# DotIO.net
KiCad netlist of a schematic drawn in EAGLE
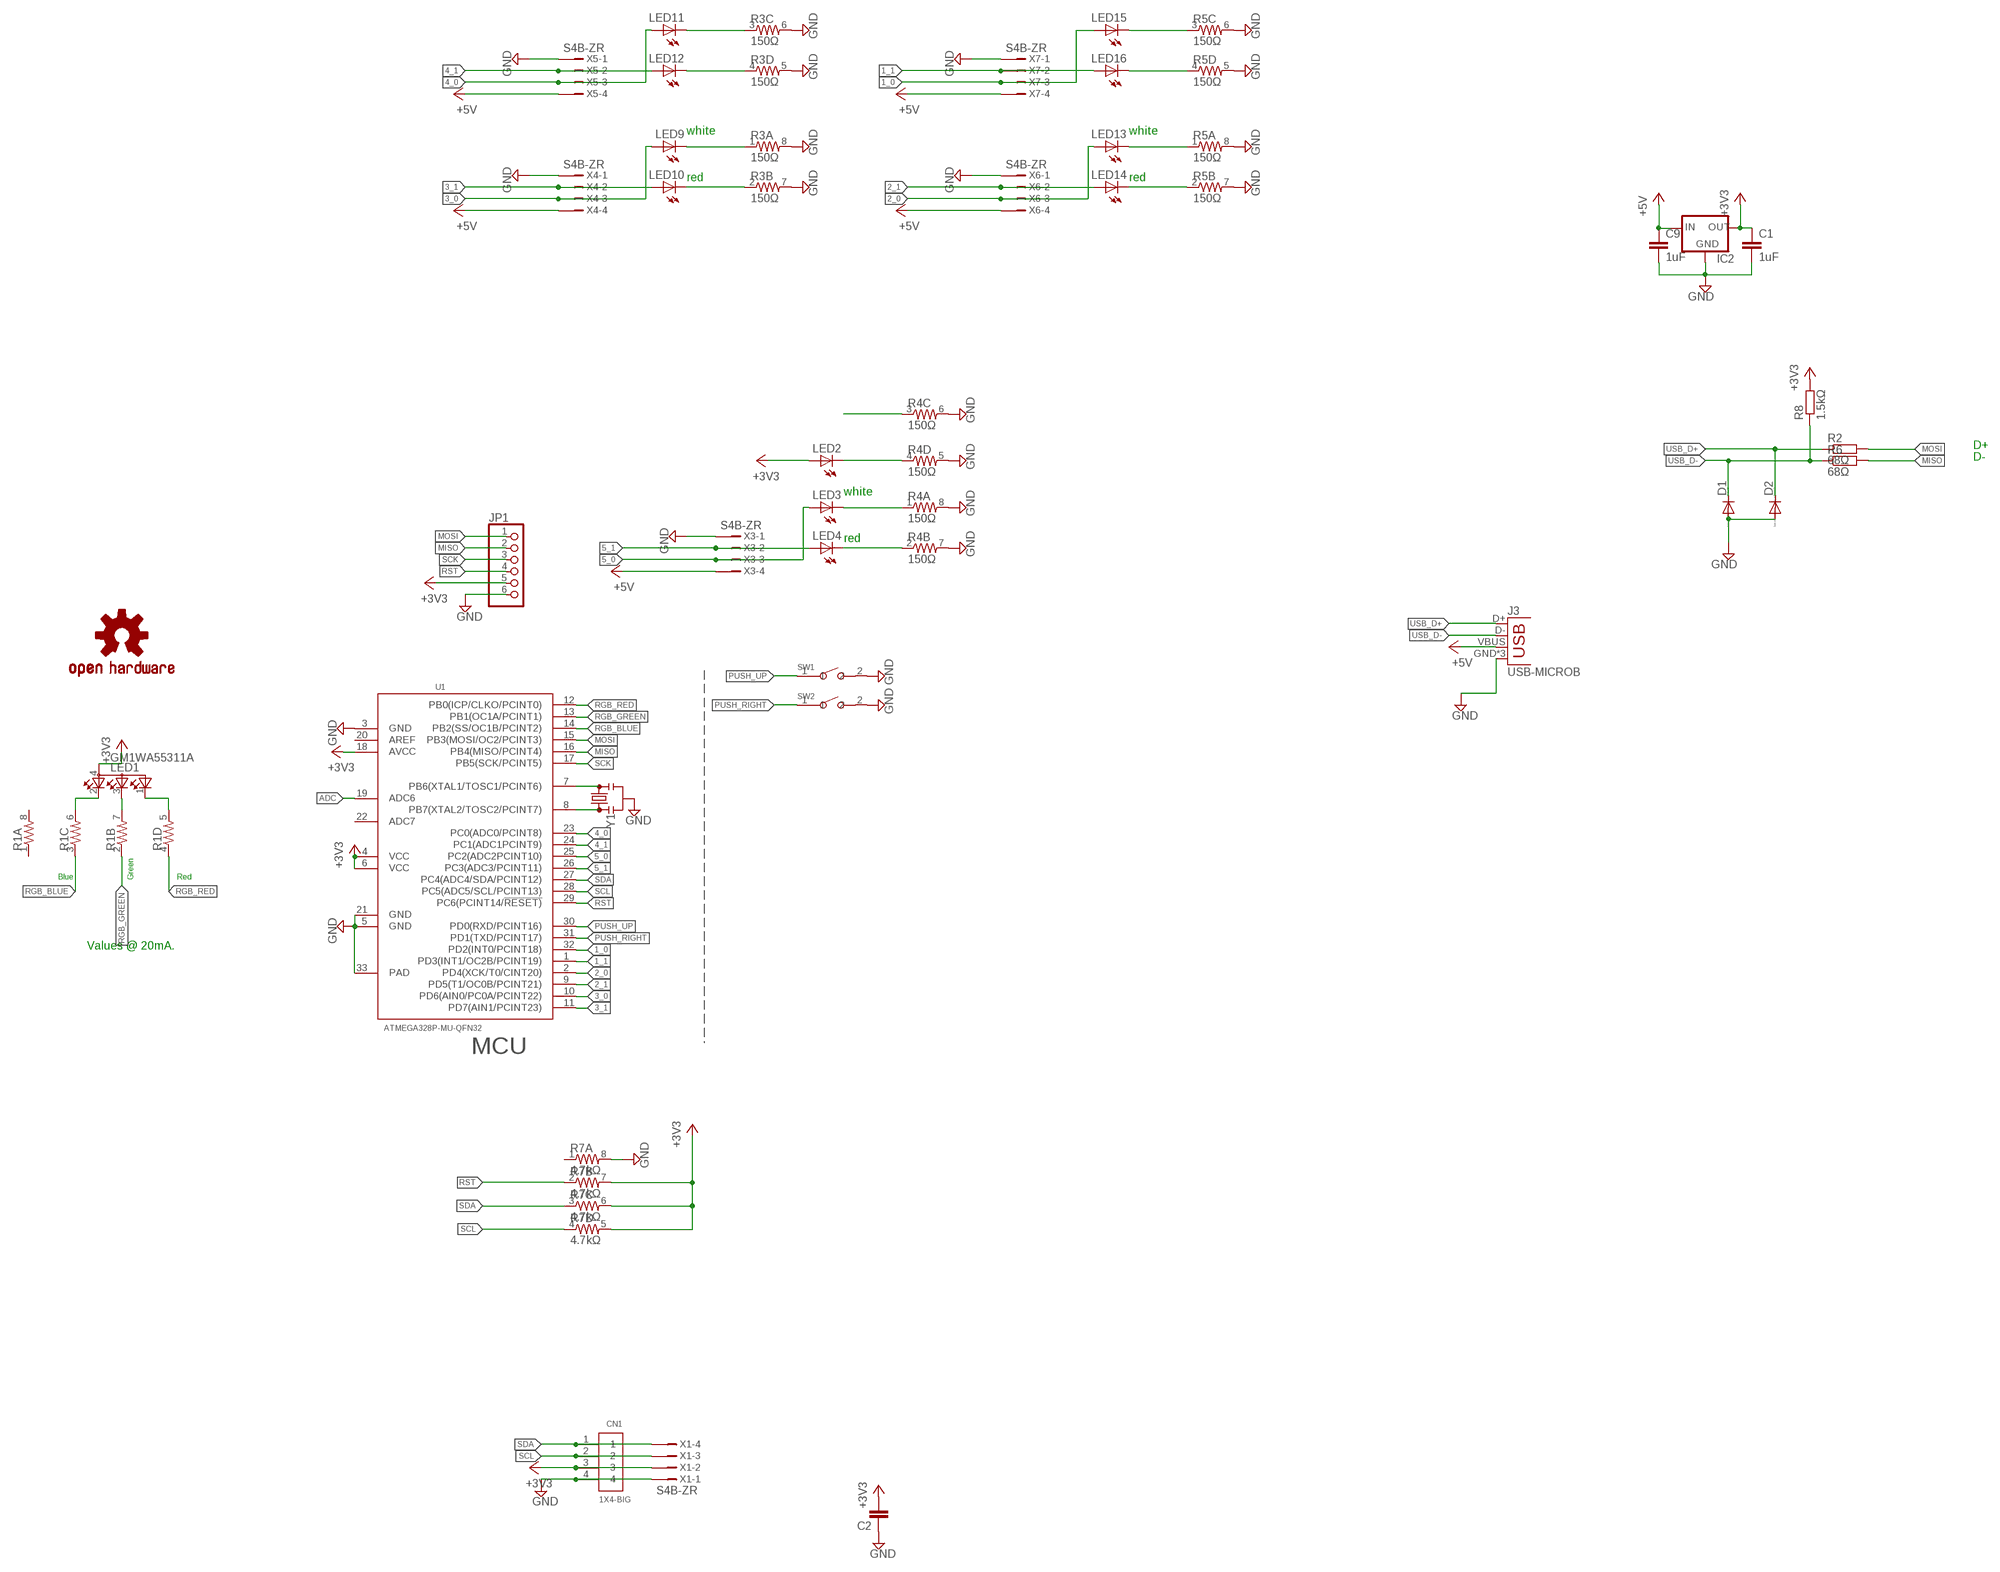
[diagram p0: schematic, sheet 1]

(export (version "E")
  (design (tool "Eeschema 10.0.6"))
  (components
    (comp (ref "C1")
      (value "1uF")
      (footprint "eagle-import:C0603")
      (libsource (lib "eagle-import") (part "C-EUC0603"))
    )
    (comp (ref "C2")
      (value "C-EUC3216")
      (footprint "eagle-import:C3216")
      (libsource (lib "eagle-import") (part "C-EUC3216"))
    )
    (comp (ref "C9")
      (value "1uF")
      (footprint "eagle-import:C0603")
      (libsource (lib "eagle-import") (part "C-EUC0603"))
    )
    (comp (ref "CN1")
      (value "1X4-BIG")
      (footprint "eagle-import:1X04-BIG")
      (libsource (lib "eagle-import") (part "1X4-BIG"))
    )
    (comp (ref "D1")
      (value "DIODE-SOD523")
      (footprint "eagle-import:SOD523")
      (libsource (lib "eagle-import") (part "DIODE-SOD523"))
    )
    (comp (ref "D2")
      (value "DIODE-SOD523")
      (footprint "eagle-import:SOD523")
      (libsource (lib "eagle-import") (part "DIODE-SOD523"))
    )
    (comp (ref "IC2")
      (value "MCP1700TT")
      (footprint "eagle-import:SOT-23")
      (libsource (lib "eagle-import") (part "MCP1700TT"))
    )
    (comp (ref "J3")
      (value "USB-MICROB")
      (footprint "eagle-import:USB-MICROB")
      (libsource (lib "eagle-import") (part "USB-MICROB"))
    )
    (comp (ref "JP1")
      (value "PINHD-1X6")
      (footprint "eagle-import:1X06")
      (libsource (lib "eagle-import") (part "PINHD-1X6"))
    )
    (comp (ref "LED1")
      (value "GM1WA55311A")
      (footprint "eagle-import:GM1WA55311A")
      (libsource (lib "eagle-import") (part "GM1WA55311A"))
    )
    (comp (ref "LED2")
      (value "LED0603")
      (footprint "eagle-import:LED-0603")
      (libsource (lib "eagle-import") (part "LED0603"))
    )
    (comp (ref "LED3")
      (value "LED0603")
      (footprint "eagle-import:LED-0603")
      (libsource (lib "eagle-import") (part "LED0603"))
    )
    (comp (ref "LED4")
      (value "LED0603")
      (footprint "eagle-import:LED-0603")
      (libsource (lib "eagle-import") (part "LED0603"))
    )
    (comp (ref "LED9")
      (value "LED0603")
      (footprint "eagle-import:LED-0603")
      (libsource (lib "eagle-import") (part "LED0603"))
    )
    (comp (ref "LED10")
      (value "LED0603")
      (footprint "eagle-import:LED-0603")
      (libsource (lib "eagle-import") (part "LED0603"))
    )
    (comp (ref "LED11")
      (value "LED0603")
      (footprint "eagle-import:LED-0603")
      (libsource (lib "eagle-import") (part "LED0603"))
    )
    (comp (ref "LED12")
      (value "LED0603")
      (footprint "eagle-import:LED-0603")
      (libsource (lib "eagle-import") (part "LED0603"))
    )
    (comp (ref "LED13")
      (value "LED0603")
      (footprint "eagle-import:LED-0603")
      (libsource (lib "eagle-import") (part "LED0603"))
    )
    (comp (ref "LED14")
      (value "LED0603")
      (footprint "eagle-import:LED-0603")
      (libsource (lib "eagle-import") (part "LED0603"))
    )
    (comp (ref "LED15")
      (value "LED0603")
      (footprint "eagle-import:LED-0603")
      (libsource (lib "eagle-import") (part "LED0603"))
    )
    (comp (ref "LED16")
      (value "LED0603")
      (footprint "eagle-import:LED-0603")
      (libsource (lib "eagle-import") (part "LED0603"))
    )
    (comp (ref "LOGO1")
      (value "OSHW-LOGOS")
      (footprint "eagle-import:OSHW-LOGO-S")
      (libsource (lib "eagle-import") (part "OSHW-LOGOS"))
    )
    (comp (ref "R1")
      (value "RESISTOR-ARRAY0603-ARV")
      (footprint "eagle-import:0603-ARV")
      (libsource (lib "eagle-import") (part "RESISTOR-ARRAY0603-ARV"))
    )
    (comp (ref "R2")
      (value "68Ω")
      (footprint "eagle-import:R0603")
      (libsource (lib "eagle-import") (part "R-EU_R0603"))
    )
    (comp (ref "R3")
      (value "150Ω")
      (footprint "eagle-import:0603-ARV")
      (libsource (lib "eagle-import") (part "RESISTOR-ARRAY0603-ARV"))
    )
    (comp (ref "R4")
      (value "150Ω")
      (footprint "eagle-import:0603-ARV")
      (libsource (lib "eagle-import") (part "RESISTOR-ARRAY0603-ARV"))
    )
    (comp (ref "R5")
      (value "150Ω")
      (footprint "eagle-import:0603-ARV")
      (libsource (lib "eagle-import") (part "RESISTOR-ARRAY0603-ARV"))
    )
    (comp (ref "R6")
      (value "68Ω")
      (footprint "eagle-import:R0603")
      (libsource (lib "eagle-import") (part "R-EU_R0603"))
    )
    (comp (ref "R7")
      (value "4.7kΩ")
      (footprint "eagle-import:0603-ARV")
      (libsource (lib "eagle-import") (part "RESISTOR-ARRAY0603-ARV"))
    )
    (comp (ref "R8")
      (value "1.5kΩ")
      (footprint "eagle-import:R0603")
      (libsource (lib "eagle-import") (part "R-EU_R0603"))
    )
    (comp (ref "SW1")
      (value "SMD-BUTTON(2P-6.0X3.0X2.5MM)-DHT-1163S")
      (footprint "eagle-import:SW2-4.0-6.0X3.0X2.5MM")
      (libsource (lib "eagle-import") (part "SMD-BUTTON(2P-6.0X3.0X2.5MM)-DHT-1163S"))
    )
    (comp (ref "SW2")
      (value "SMD-BUTTON(2P-6.0X3.0X2.5MM)-DHT-1163S")
      (footprint "eagle-import:SW2-4.0-6.0X3.0X2.5MM")
      (libsource (lib "eagle-import") (part "SMD-BUTTON(2P-6.0X3.0X2.5MM)-DHT-1163S"))
    )
    (comp (ref "U1")
      (value "ATMEGA328P-MU-QFN32")
      (footprint "eagle-import:QFN32G-0.5-5X5MM")
      (fields (field (name "MPN") "ATMEGA328P-MU"))
      (libsource (lib "eagle-import") (part "MCU-ATMEGA328P-MU(QFN32)"))
    )
    (comp (ref "X1")
      (value "S4B-ZR")
      (footprint "eagle-import:S4B-ZR")
      (fields (field (name "MF") "FARNELL") (field (name "MPN") "S4B-ZR(LF)(SN)"))
      (libsource (lib "eagle-import") (part "?4B-ZRS"))
    )
    (comp (ref "X3")
      (value "S4B-ZR")
      (footprint "eagle-import:S4B-ZR")
      (fields (field (name "MF") "FARNELL") (field (name "MPN") "S4B-ZR(LF)(SN)"))
      (libsource (lib "eagle-import") (part "?4B-ZRS"))
    )
    (comp (ref "X4")
      (value "S4B-ZR")
      (footprint "eagle-import:S4B-ZR")
      (fields (field (name "MF") "FARNELL") (field (name "MPN") "S4B-ZR(LF)(SN)"))
      (libsource (lib "eagle-import") (part "?4B-ZRS"))
    )
    (comp (ref "X5")
      (value "S4B-ZR")
      (footprint "eagle-import:S4B-ZR")
      (fields (field (name "MF") "FARNELL") (field (name "MPN") "S4B-ZR(LF)(SN)"))
      (libsource (lib "eagle-import") (part "?4B-ZRS"))
    )
    (comp (ref "X6")
      (value "S4B-ZR")
      (footprint "eagle-import:S4B-ZR")
      (fields (field (name "MF") "FARNELL") (field (name "MPN") "S4B-ZR(LF)(SN)"))
      (libsource (lib "eagle-import") (part "?4B-ZRS"))
    )
    (comp (ref "X7")
      (value "S4B-ZR")
      (footprint "eagle-import:S4B-ZR")
      (fields (field (name "MF") "FARNELL") (field (name "MPN") "S4B-ZR(LF)(SN)"))
      (libsource (lib "eagle-import") (part "?4B-ZRS"))
    )
    (comp (ref "Y1")
      (value "RESONATORSMD-3.2X1.3")
      (footprint "eagle-import:RESONATOR-SMD-3.2X1.3")
      (libsource (lib "eagle-import") (part "RESONATORSMD-3.2X1.3"))
    )
  )
  (nets
    (net (code "1") (name "+3V3") (class "Default")
      (node (ref "C1") (pin "1") (pinfunction "1_1") (pintype "passive"))
      (node (ref "C2") (pin "2") (pinfunction "2_2") (pintype "passive"))
      (node (ref "CN1") (pin "3") (pinfunction "3_3") (pintype "bidirectional"))
      (node (ref "IC2") (pin "2") (pinfunction "OUT_2") (pintype "passive"))
      (node (ref "JP1") (pin "5") (pinfunction "5_5") (pintype "passive"))
      (node (ref "LED1") (pin "4") (pinfunction "A_4") (pintype "passive"))
      (node (ref "LED2") (pin "A") (pinfunction "A_A") (pintype "passive"))
      (node (ref "R7") (pin "5") (pinfunction "2_5") (pintype "passive"))
      (node (ref "R7") (pin "6") (pinfunction "2_6") (pintype "passive"))
      (node (ref "R7") (pin "7") (pinfunction "2_7") (pintype "passive"))
      (node (ref "R8") (pin "2") (pinfunction "2_2") (pintype "passive"))
      (node (ref "U1") (pin "18") (pinfunction "AVCC_18") (pintype "bidirectional"))
      (node (ref "U1") (pin "4") (pinfunction "VCC_4") (pintype "bidirectional"))
      (node (ref "U1") (pin "6") (pinfunction "VCC_6") (pintype "bidirectional"))
      (node (ref "X1") (pin "2") (pinfunction "1_2") (pintype "passive"))
    )
    (net (code "2") (name "+5V") (class "Default")
      (node (ref "C9") (pin "1") (pinfunction "1_1") (pintype "passive"))
      (node (ref "IC2") (pin "3") (pinfunction "IN_3") (pintype "input"))
      (node (ref "J3") (pin "VBUS") (pinfunction "VBUS_VBUS") (pintype "bidirectional"))
      (node (ref "X3") (pin "4") (pinfunction "1_4") (pintype "passive"))
      (node (ref "X4") (pin "4") (pinfunction "1_4") (pintype "passive"))
      (node (ref "X5") (pin "4") (pinfunction "1_4") (pintype "passive"))
      (node (ref "X6") (pin "4") (pinfunction "1_4") (pintype "passive"))
      (node (ref "X7") (pin "4") (pinfunction "1_4") (pintype "passive"))
    )
    (net (code "3") (name "1_0") (class "Default")
      (node (ref "LED15") (pin "A") (pinfunction "A_A") (pintype "passive"))
      (node (ref "U1") (pin "32") (pinfunction "PD2(INT0/PCINT18)_32") (pintype "bidirectional"))
      (node (ref "X7") (pin "3") (pinfunction "1_3") (pintype "passive"))
    )
    (net (code "4") (name "1_1") (class "Default")
      (node (ref "LED16") (pin "A") (pinfunction "A_A") (pintype "passive"))
      (node (ref "U1") (pin "1") (pinfunction "PD3(INT1/OC2B/PCINT19)_1") (pintype "bidirectional"))
      (node (ref "X7") (pin "2") (pinfunction "1_2") (pintype "passive"))
    )
    (net (code "5") (name "2_0") (class "Default")
      (node (ref "LED13") (pin "A") (pinfunction "A_A") (pintype "passive"))
      (node (ref "U1") (pin "2") (pinfunction "PD4(XCK/T0/CINT20)_2") (pintype "bidirectional"))
      (node (ref "X6") (pin "3") (pinfunction "1_3") (pintype "passive"))
    )
    (net (code "6") (name "2_1") (class "Default")
      (node (ref "LED14") (pin "A") (pinfunction "A_A") (pintype "passive"))
      (node (ref "U1") (pin "9") (pinfunction "PD5(T1/OC0B/PCINT21)_9") (pintype "bidirectional"))
      (node (ref "X6") (pin "2") (pinfunction "1_2") (pintype "passive"))
    )
    (net (code "7") (name "3_0") (class "Default")
      (node (ref "LED9") (pin "A") (pinfunction "A_A") (pintype "passive"))
      (node (ref "U1") (pin "10") (pinfunction "PD6(AIN0/PC0A/PCINT22)_10") (pintype "bidirectional"))
      (node (ref "X4") (pin "3") (pinfunction "1_3") (pintype "passive"))
    )
    (net (code "8") (name "3_1") (class "Default")
      (node (ref "LED10") (pin "A") (pinfunction "A_A") (pintype "passive"))
      (node (ref "U1") (pin "11") (pinfunction "PD7(AIN1/PCINT23)_11") (pintype "bidirectional"))
      (node (ref "X4") (pin "2") (pinfunction "1_2") (pintype "passive"))
    )
    (net (code "9") (name "4_0") (class "Default")
      (node (ref "LED11") (pin "A") (pinfunction "A_A") (pintype "passive"))
      (node (ref "U1") (pin "23") (pinfunction "PC0(ADC0/PCINT8)_23") (pintype "bidirectional"))
      (node (ref "X5") (pin "3") (pinfunction "1_3") (pintype "passive"))
    )
    (net (code "10") (name "4_1") (class "Default")
      (node (ref "LED12") (pin "A") (pinfunction "A_A") (pintype "passive"))
      (node (ref "U1") (pin "24") (pinfunction "PC1(ADC1PCINT9)_24") (pintype "bidirectional"))
      (node (ref "X5") (pin "2") (pinfunction "1_2") (pintype "passive"))
    )
    (net (code "11") (name "5_0") (class "Default")
      (node (ref "LED3") (pin "A") (pinfunction "A_A") (pintype "passive"))
      (node (ref "U1") (pin "25") (pinfunction "PC2(ADC2PCINT10)_25") (pintype "bidirectional"))
      (node (ref "X3") (pin "3") (pinfunction "1_3") (pintype "passive"))
    )
    (net (code "12") (name "5_1") (class "Default")
      (node (ref "LED4") (pin "A") (pinfunction "A_A") (pintype "passive"))
      (node (ref "U1") (pin "26") (pinfunction "PC3(ADC3/PCINT11)_26") (pintype "bidirectional"))
      (node (ref "X3") (pin "2") (pinfunction "1_2") (pintype "passive"))
    )
    (net (code "13") (name "ADC") (class "Default")
      (node (ref "U1") (pin "19") (pinfunction "ADC6_19") (pintype "bidirectional"))
    )
    (net (code "14") (name "GND") (class "Default")
      (node (ref "C1") (pin "2") (pinfunction "2_2") (pintype "passive"))
      (node (ref "C2") (pin "1") (pinfunction "1_1") (pintype "passive"))
      (node (ref "C9") (pin "2") (pinfunction "2_2") (pintype "passive"))
      (node (ref "CN1") (pin "4") (pinfunction "4_4") (pintype "bidirectional"))
      (node (ref "D1") (pin "A") (pinfunction "A_A") (pintype "passive"))
      (node (ref "D2") (pin "A") (pinfunction "A_A") (pintype "passive"))
      (node (ref "IC2") (pin "1") (pinfunction "GND_1") (pintype "input"))
      (node (ref "J3") (pin "GND") (pinfunction "GND_GND") (pintype "bidirectional"))
      (node (ref "J3") (pin "MT1") (pinfunction "GND_MT1") (pintype "bidirectional"))
      (node (ref "J3") (pin "MT2") (pinfunction "GND_MT2") (pintype "bidirectional"))
      (node (ref "JP1") (pin "6") (pinfunction "6_6") (pintype "passive"))
      (node (ref "R3") (pin "5") (pinfunction "2_5") (pintype "passive"))
      (node (ref "R3") (pin "6") (pinfunction "2_6") (pintype "passive"))
      (node (ref "R3") (pin "7") (pinfunction "2_7") (pintype "passive"))
      (node (ref "R3") (pin "8") (pinfunction "2_8") (pintype "passive"))
      (node (ref "R4") (pin "5") (pinfunction "2_5") (pintype "passive"))
      (node (ref "R4") (pin "6") (pinfunction "2_6") (pintype "passive"))
      (node (ref "R4") (pin "7") (pinfunction "2_7") (pintype "passive"))
      (node (ref "R4") (pin "8") (pinfunction "2_8") (pintype "passive"))
      (node (ref "R5") (pin "5") (pinfunction "2_5") (pintype "passive"))
      (node (ref "R5") (pin "6") (pinfunction "2_6") (pintype "passive"))
      (node (ref "R5") (pin "7") (pinfunction "2_7") (pintype "passive"))
      (node (ref "R5") (pin "8") (pinfunction "2_8") (pintype "passive"))
      (node (ref "R7") (pin "8") (pinfunction "2_8") (pintype "passive"))
      (node (ref "SW1") (pin "2") (pinfunction "2_2") (pintype "bidirectional"))
      (node (ref "SW2") (pin "2") (pinfunction "2_2") (pintype "bidirectional"))
      (node (ref "U1") (pin "21") (pinfunction "GND_21") (pintype "bidirectional"))
      (node (ref "U1") (pin "3") (pinfunction "GND_3") (pintype "bidirectional"))
      (node (ref "U1") (pin "33") (pinfunction "PAD_33") (pintype "bidirectional"))
      (node (ref "U1") (pin "5") (pinfunction "GND_5") (pintype "bidirectional"))
      (node (ref "X1") (pin "1") (pinfunction "1_1") (pintype "passive"))
      (node (ref "X3") (pin "1") (pinfunction "1_1") (pintype "passive"))
      (node (ref "X4") (pin "1") (pinfunction "1_1") (pintype "passive"))
      (node (ref "X5") (pin "1") (pinfunction "1_1") (pintype "passive"))
      (node (ref "X6") (pin "1") (pinfunction "1_1") (pintype "passive"))
      (node (ref "X7") (pin "1") (pinfunction "1_1") (pintype "passive"))
      (node (ref "Y1") (pin "2") (pinfunction "2_2") (pintype "passive"))
    )
    (net (code "15") (name "MISO") (class "Default")
      (node (ref "JP1") (pin "2") (pinfunction "2_2") (pintype "passive"))
      (node (ref "R6") (pin "2") (pinfunction "2_2") (pintype "passive"))
      (node (ref "U1") (pin "16") (pinfunction "PB4(MISO/PCINT4)_16") (pintype "bidirectional"))
    )
    (net (code "16") (name "MOSI") (class "Default")
      (node (ref "JP1") (pin "1") (pinfunction "1_1") (pintype "passive"))
      (node (ref "R2") (pin "2") (pinfunction "2_2") (pintype "passive"))
      (node (ref "U1") (pin "15") (pinfunction "PB3(MOSI/OC2/PCINT3)_15") (pintype "bidirectional"))
    )
    (net (code "17") (name "Net-(LED1-CBLUE)") (class "Default")
      (node (ref "LED1") (pin "3") (pinfunction "CBLUE_3") (pintype "passive"))
      (node (ref "R1") (pin "7") (pinfunction "2_7") (pintype "passive"))
    )
    (net (code "18") (name "Net-(LED1-CGREEN)") (class "Default")
      (node (ref "LED1") (pin "1") (pinfunction "CGREEN_1") (pintype "passive"))
      (node (ref "R1") (pin "5") (pinfunction "2_5") (pintype "passive"))
    )
    (net (code "19") (name "Net-(LED1-CRED)") (class "Default")
      (node (ref "LED1") (pin "2") (pinfunction "CRED_2") (pintype "passive"))
      (node (ref "R1") (pin "6") (pinfunction "2_6") (pintype "passive"))
    )
    (net (code "20") (name "Net-(LED3-PadC)") (class "Default")
      (node (ref "LED3") (pin "C") (pinfunction "C_C") (pintype "passive"))
      (node (ref "R4") (pin "1") (pinfunction "1_1") (pintype "passive"))
    )
    (net (code "21") (name "Net-(LED9-PadC)") (class "Default")
      (node (ref "LED9") (pin "C") (pinfunction "C_C") (pintype "passive"))
      (node (ref "R3") (pin "1") (pinfunction "1_1") (pintype "passive"))
    )
    (net (code "22") (name "Net-(LED13-PadC)") (class "Default")
      (node (ref "LED13") (pin "C") (pinfunction "C_C") (pintype "passive"))
      (node (ref "R5") (pin "1") (pinfunction "1_1") (pintype "passive"))
    )
    (net (code "23") (name "Net-(R3B-1)") (class "Default")
      (node (ref "LED10") (pin "C") (pinfunction "C_C") (pintype "passive"))
      (node (ref "R3") (pin "2") (pinfunction "1_2") (pintype "passive"))
    )
    (net (code "24") (name "Net-(R3C-1)") (class "Default")
      (node (ref "LED11") (pin "C") (pinfunction "C_C") (pintype "passive"))
      (node (ref "R3") (pin "3") (pinfunction "1_3") (pintype "passive"))
    )
    (net (code "25") (name "Net-(R3D-1)") (class "Default")
      (node (ref "LED12") (pin "C") (pinfunction "C_C") (pintype "passive"))
      (node (ref "R3") (pin "4") (pinfunction "1_4") (pintype "passive"))
    )
    (net (code "26") (name "Net-(R4B-1)") (class "Default")
      (node (ref "LED4") (pin "C") (pinfunction "C_C") (pintype "passive"))
      (node (ref "R4") (pin "2") (pinfunction "1_2") (pintype "passive"))
    )
    (net (code "27") (name "Net-(R4D-1)") (class "Default")
      (node (ref "LED2") (pin "C") (pinfunction "C_C") (pintype "passive"))
      (node (ref "R4") (pin "4") (pinfunction "1_4") (pintype "passive"))
    )
    (net (code "28") (name "Net-(R5B-1)") (class "Default")
      (node (ref "LED14") (pin "C") (pinfunction "C_C") (pintype "passive"))
      (node (ref "R5") (pin "2") (pinfunction "1_2") (pintype "passive"))
    )
    (net (code "29") (name "Net-(R5C-1)") (class "Default")
      (node (ref "LED15") (pin "C") (pinfunction "C_C") (pintype "passive"))
      (node (ref "R5") (pin "3") (pinfunction "1_3") (pintype "passive"))
    )
    (net (code "30") (name "Net-(R5D-1)") (class "Default")
      (node (ref "LED16") (pin "C") (pinfunction "C_C") (pintype "passive"))
      (node (ref "R5") (pin "4") (pinfunction "1_4") (pintype "passive"))
    )
    (net (code "31") (name "Net-(U1-PB6(XTAL1{slash}TOSC1{slash}PCINT6))") (class "Default")
      (node (ref "U1") (pin "7") (pinfunction "PB6(XTAL1/TOSC1/PCINT6)_7") (pintype "bidirectional"))
      (node (ref "Y1") (pin "3") (pinfunction "3_3") (pintype "passive"))
    )
    (net (code "32") (name "Net-(U1-PB7(XTAL2{slash}TOSC2{slash}PCINT7))") (class "Default")
      (node (ref "U1") (pin "8") (pinfunction "PB7(XTAL2/TOSC2/PCINT7)_8") (pintype "bidirectional"))
      (node (ref "Y1") (pin "1") (pinfunction "1_1") (pintype "passive"))
    )
    (net (code "33") (name "PUSH_RIGHT") (class "Default")
      (node (ref "SW2") (pin "1") (pinfunction "1_1") (pintype "bidirectional"))
      (node (ref "U1") (pin "31") (pinfunction "PD1(TXD/PCINT17)_31") (pintype "bidirectional"))
    )
    (net (code "34") (name "PUSH_UP") (class "Default")
      (node (ref "SW1") (pin "1") (pinfunction "1_1") (pintype "bidirectional"))
      (node (ref "U1") (pin "30") (pinfunction "PD0(RXD/PCINT16)_30") (pintype "bidirectional"))
    )
    (net (code "35") (name "RGB_BLUE") (class "Default")
      (node (ref "R1") (pin "3") (pinfunction "1_3") (pintype "passive"))
      (node (ref "U1") (pin "14") (pinfunction "PB2(SS/OC1B/PCINT2)_14") (pintype "bidirectional"))
    )
    (net (code "36") (name "RGB_GREEN") (class "Default")
      (node (ref "R1") (pin "2") (pinfunction "1_2") (pintype "passive"))
      (node (ref "U1") (pin "13") (pinfunction "PB1(OC1A/PCINT1)_13") (pintype "bidirectional"))
    )
    (net (code "37") (name "RGB_RED") (class "Default")
      (node (ref "R1") (pin "4") (pinfunction "1_4") (pintype "passive"))
      (node (ref "U1") (pin "12") (pinfunction "PB0(ICP/CLKO/PCINT0)_12") (pintype "bidirectional"))
    )
    (net (code "38") (name "RST") (class "Default")
      (node (ref "JP1") (pin "4") (pinfunction "4_4") (pintype "passive"))
      (node (ref "R7") (pin "2") (pinfunction "1_2") (pintype "passive"))
      (node (ref "U1") (pin "29") (pinfunction "PC6(PCINT14/~{RESET})_29") (pintype "bidirectional"))
    )
    (net (code "39") (name "SCK") (class "Default")
      (node (ref "JP1") (pin "3") (pinfunction "3_3") (pintype "passive"))
      (node (ref "U1") (pin "17") (pinfunction "PB5(SCK/PCINT5)_17") (pintype "bidirectional"))
    )
    (net (code "40") (name "SCL") (class "Default")
      (node (ref "CN1") (pin "2") (pinfunction "2_2") (pintype "bidirectional"))
      (node (ref "R7") (pin "4") (pinfunction "1_4") (pintype "passive"))
      (node (ref "U1") (pin "28") (pinfunction "PC5(ADC5/SCL/PCINT13)_28") (pintype "bidirectional"))
      (node (ref "X1") (pin "3") (pinfunction "1_3") (pintype "passive"))
    )
    (net (code "41") (name "SDA") (class "Default")
      (node (ref "CN1") (pin "1") (pinfunction "1_1") (pintype "bidirectional"))
      (node (ref "R7") (pin "3") (pinfunction "1_3") (pintype "passive"))
      (node (ref "U1") (pin "27") (pinfunction "PC4(ADC4/SDA/PCINT12)_27") (pintype "bidirectional"))
      (node (ref "X1") (pin "4") (pinfunction "1_4") (pintype "passive"))
    )
    (net (code "42") (name "USB_D+") (class "Default")
      (node (ref "D2") (pin "C") (pinfunction "C_C") (pintype "passive"))
      (node (ref "J3") (pin "D+") (pinfunction "D+_D+") (pintype "bidirectional"))
      (node (ref "R2") (pin "1") (pinfunction "1_1") (pintype "passive"))
    )
    (net (code "43") (name "USB_D-") (class "Default")
      (node (ref "D1") (pin "C") (pinfunction "C_C") (pintype "passive"))
      (node (ref "J3") (pin "D-") (pinfunction "D-_D-") (pintype "bidirectional"))
      (node (ref "R6") (pin "1") (pinfunction "1_1") (pintype "passive"))
      (node (ref "R8") (pin "1") (pinfunction "1_1") (pintype "passive"))
    )
    (net (code "44") (name "unconnected-(R1-Pad1)") (class "Default")
      (node (ref "R1") (pin "1") (pinfunction "1_1") (pintype "passive"))
    )
    (net (code "45") (name "unconnected-(R1A-2-Pad8)") (class "Default")
      (node (ref "R1") (pin "8") (pinfunction "2_8") (pintype "passive"))
    )
    (net (code "46") (name "unconnected-(R4C-1-Pad3)") (class "Default")
      (node (ref "R4") (pin "3") (pinfunction "1_3") (pintype "passive"))
    )
    (net (code "47") (name "unconnected-(R7-Pad1)") (class "Default")
      (node (ref "R7") (pin "1") (pinfunction "1_1") (pintype "passive"))
    )
    (net (code "48") (name "unconnected-(U1-ADC7-Pad22)") (class "Default")
      (node (ref "U1") (pin "22") (pinfunction "ADC7_22") (pintype "bidirectional"))
    )
    (net (code "49") (name "unconnected-(U1-AREF-Pad20)") (class "Default")
      (node (ref "U1") (pin "20") (pinfunction "AREF_20") (pintype "bidirectional"))
    )
  )
)
